# l293d.net
KiCad netlist of a schematic drawn in EAGLE
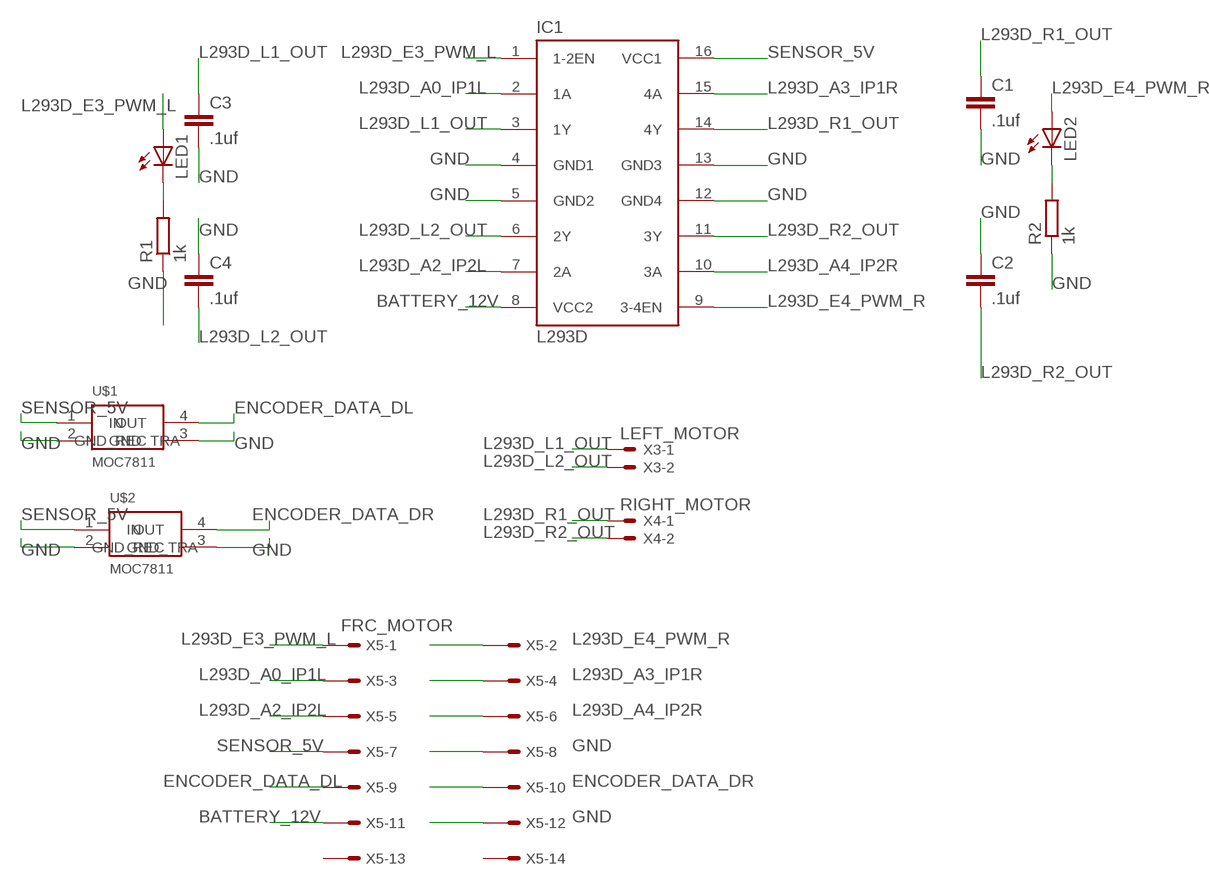
[diagram p0: schematic, sheet 1]

(export (version "E")
  (design (tool "Eeschema 10.0.6"))
  (components
    (comp (ref "C1")
      (value ".1uf")
      (footprint "eagle-import:C1206")
      (libsource (lib "eagle-import") (part "C-EUC1206"))
    )
    (comp (ref "C2")
      (value ".1uf")
      (footprint "eagle-import:C1206")
      (libsource (lib "eagle-import") (part "C-EUC1206"))
    )
    (comp (ref "C3")
      (value ".1uf")
      (footprint "eagle-import:C1206")
      (libsource (lib "eagle-import") (part "C-EUC1206"))
    )
    (comp (ref "C4")
      (value ".1uf")
      (footprint "eagle-import:C1206")
      (libsource (lib "eagle-import") (part "C-EUC1206"))
    )
    (comp (ref "IC1")
      (value "L293D")
      (footprint "eagle-import:DIL16")
      (libsource (lib "eagle-import") (part "L293D"))
    )
    (comp (ref "LED1")
      (value "LEDSMT1206")
      (footprint "eagle-import:1206")
      (libsource (lib "eagle-import") (part "LEDSMT1206"))
    )
    (comp (ref "LED2")
      (value "LEDSMT1206")
      (footprint "eagle-import:1206")
      (libsource (lib "eagle-import") (part "LEDSMT1206"))
    )
    (comp (ref "R1")
      (value "1k")
      (footprint "eagle-import:M1206")
      (libsource (lib "eagle-import") (part "R-EU_M1206"))
    )
    (comp (ref "R2")
      (value "1k")
      (footprint "eagle-import:M1206")
      (libsource (lib "eagle-import") (part "R-EU_M1206"))
    )
    (comp (ref "U$1")
      (value "MOC7811")
      (footprint "eagle-import:THROUGH_HOLE_NORMAL")
      (libsource (lib "eagle-import") (part "MOC7811"))
    )
    (comp (ref "U$2")
      (value "MOC7811")
      (footprint "eagle-import:THROUGH_HOLE_NORMAL")
      (libsource (lib "eagle-import") (part "MOC7811"))
    )
    (comp (ref "X3")
      (value "LEFT_MOTOR")
      (footprint "eagle-import:22-23-2021")
      (fields (field (name "MF") "MOLEX") (field (name "MPN") "22-23-2021"))
      (libsource (lib "eagle-import") (part "22-23-2021"))
    )
    (comp (ref "X4")
      (value "RIGHT_MOTOR")
      (footprint "eagle-import:22-23-2021")
      (fields (field (name "MF") "MOLEX") (field (name "MPN") "22-23-2021"))
      (libsource (lib "eagle-import") (part "22-23-2021"))
    )
    (comp (ref "X5")
      (value "FRC_MOTOR")
      (footprint "eagle-import:057-014-1")
      (libsource (lib "eagle-import") (part "057-014-1"))
    )
  )
  (nets
    (net (code "1") (name "/BATTERY_12V") (class "Default")
      (node (ref "IC1") (pin "8") (pinfunction "VCC2_8") (pintype "power_in"))
      (node (ref "X5") (pin "11") (pinfunction "S_11") (pintype "passive"))
    )
    (net (code "2") (name "/ENCODER_DATA_DL") (class "Default")
      (node (ref "U$1") (pin "4") (pinfunction "OUT_4") (pintype "bidirectional"))
      (node (ref "X5") (pin "9") (pinfunction "S_9") (pintype "passive"))
    )
    (net (code "3") (name "/ENCODER_DATA_DR") (class "Default")
      (node (ref "U$2") (pin "4") (pinfunction "OUT_4") (pintype "bidirectional"))
      (node (ref "X5") (pin "10") (pinfunction "S_10") (pintype "passive"))
    )
    (net (code "4") (name "/GND") (class "Default")
      (node (ref "C1") (pin "2") (pinfunction "2_2") (pintype "passive"))
      (node (ref "C2") (pin "1") (pinfunction "1_1") (pintype "passive"))
      (node (ref "C3") (pin "2") (pinfunction "2_2") (pintype "passive"))
      (node (ref "C4") (pin "1") (pinfunction "1_1") (pintype "passive"))
      (node (ref "IC1") (pin "12") (pinfunction "GND4_12") (pintype "power_in"))
      (node (ref "IC1") (pin "13") (pinfunction "GND3_13") (pintype "power_in"))
      (node (ref "IC1") (pin "4") (pinfunction "GND1_4") (pintype "power_in"))
      (node (ref "IC1") (pin "5") (pinfunction "GND2_5") (pintype "power_in"))
      (node (ref "R1") (pin "1") (pinfunction "1_1") (pintype "passive"))
      (node (ref "R2") (pin "1") (pinfunction "1_1") (pintype "passive"))
      (node (ref "U$1") (pin "2") (pinfunction "GND_TRA_2") (pintype "bidirectional"))
      (node (ref "U$1") (pin "3") (pinfunction "GND_REC_3") (pintype "bidirectional"))
      (node (ref "U$2") (pin "2") (pinfunction "GND_TRA_2") (pintype "bidirectional"))
      (node (ref "U$2") (pin "3") (pinfunction "GND_REC_3") (pintype "bidirectional"))
      (node (ref "X5") (pin "12") (pinfunction "S_12") (pintype "passive"))
      (node (ref "X5") (pin "8") (pinfunction "S_8") (pintype "passive"))
    )
    (net (code "5") (name "/L293D_A0_IP1L") (class "Default")
      (node (ref "IC1") (pin "2") (pinfunction "1A_2") (pintype "input"))
      (node (ref "X5") (pin "3") (pinfunction "S_3") (pintype "passive"))
    )
    (net (code "6") (name "/L293D_A2_IP2L") (class "Default")
      (node (ref "IC1") (pin "7") (pinfunction "2A_7") (pintype "input"))
      (node (ref "X5") (pin "5") (pinfunction "S_5") (pintype "passive"))
    )
    (net (code "7") (name "/L293D_A3_IP1R") (class "Default")
      (node (ref "IC1") (pin "15") (pinfunction "4A_15") (pintype "input"))
      (node (ref "X5") (pin "4") (pinfunction "S_4") (pintype "passive"))
    )
    (net (code "8") (name "/L293D_A4_IP2R") (class "Default")
      (node (ref "IC1") (pin "10") (pinfunction "3A_10") (pintype "input"))
      (node (ref "X5") (pin "6") (pinfunction "S_6") (pintype "passive"))
    )
    (net (code "9") (name "/L293D_E3_PWM_L") (class "Default")
      (node (ref "IC1") (pin "1") (pinfunction "1-2EN_1") (pintype "input"))
      (node (ref "LED1") (pin "A") (pinfunction "A_A") (pintype "passive"))
      (node (ref "X5") (pin "1") (pinfunction "S_1") (pintype "passive"))
    )
    (net (code "10") (name "/L293D_E4_PWM_R") (class "Default")
      (node (ref "IC1") (pin "9") (pinfunction "3-4EN_9") (pintype "input"))
      (node (ref "LED2") (pin "A") (pinfunction "A_A") (pintype "passive"))
      (node (ref "X5") (pin "2") (pinfunction "S_2") (pintype "passive"))
    )
    (net (code "11") (name "/L293D_L1_OUT") (class "Default")
      (node (ref "C3") (pin "1") (pinfunction "1_1") (pintype "passive"))
      (node (ref "IC1") (pin "3") (pinfunction "1Y_3") (pintype "output"))
      (node (ref "X3") (pin "1") (pinfunction "S_1") (pintype "passive"))
    )
    (net (code "12") (name "/L293D_L2_OUT") (class "Default")
      (node (ref "C4") (pin "2") (pinfunction "2_2") (pintype "passive"))
      (node (ref "IC1") (pin "6") (pinfunction "2Y_6") (pintype "output"))
      (node (ref "X3") (pin "2") (pinfunction "S_2") (pintype "passive"))
    )
    (net (code "13") (name "/L293D_R1_OUT") (class "Default")
      (node (ref "C1") (pin "1") (pinfunction "1_1") (pintype "passive"))
      (node (ref "IC1") (pin "14") (pinfunction "4Y_14") (pintype "output"))
      (node (ref "X4") (pin "1") (pinfunction "S_1") (pintype "passive"))
    )
    (net (code "14") (name "/L293D_R2_OUT") (class "Default")
      (node (ref "C2") (pin "2") (pinfunction "2_2") (pintype "passive"))
      (node (ref "IC1") (pin "11") (pinfunction "3Y_11") (pintype "output"))
      (node (ref "X4") (pin "2") (pinfunction "S_2") (pintype "passive"))
    )
    (net (code "15") (name "/SENSOR_5V") (class "Default")
      (node (ref "IC1") (pin "16") (pinfunction "VCC1_16") (pintype "power_in"))
      (node (ref "U$1") (pin "1") (pinfunction "IN_1") (pintype "bidirectional"))
      (node (ref "U$2") (pin "1") (pinfunction "IN_1") (pintype "bidirectional"))
      (node (ref "X5") (pin "7") (pinfunction "S_7") (pintype "passive"))
    )
    (net (code "16") (name "Net-(LED1-PadC)") (class "Default")
      (node (ref "LED1") (pin "C") (pinfunction "C_C") (pintype "passive"))
      (node (ref "R1") (pin "2") (pinfunction "2_2") (pintype "passive"))
    )
    (net (code "17") (name "Net-(LED2-PadC)") (class "Default")
      (node (ref "LED2") (pin "C") (pinfunction "C_C") (pintype "passive"))
      (node (ref "R2") (pin "2") (pinfunction "2_2") (pintype "passive"))
    )
    (net (code "18") (name "unconnected-(X5E-S-Pad13)") (class "Default")
      (node (ref "X5") (pin "13") (pinfunction "S_13") (pintype "passive"))
    )
    (net (code "19") (name "unconnected-(X5F-S-Pad14)") (class "Default")
      (node (ref "X5") (pin "14") (pinfunction "S_14") (pintype "passive"))
    )
  )
)
